# MCU.net
KiCad netlist of a schematic drawn in Altium Designer
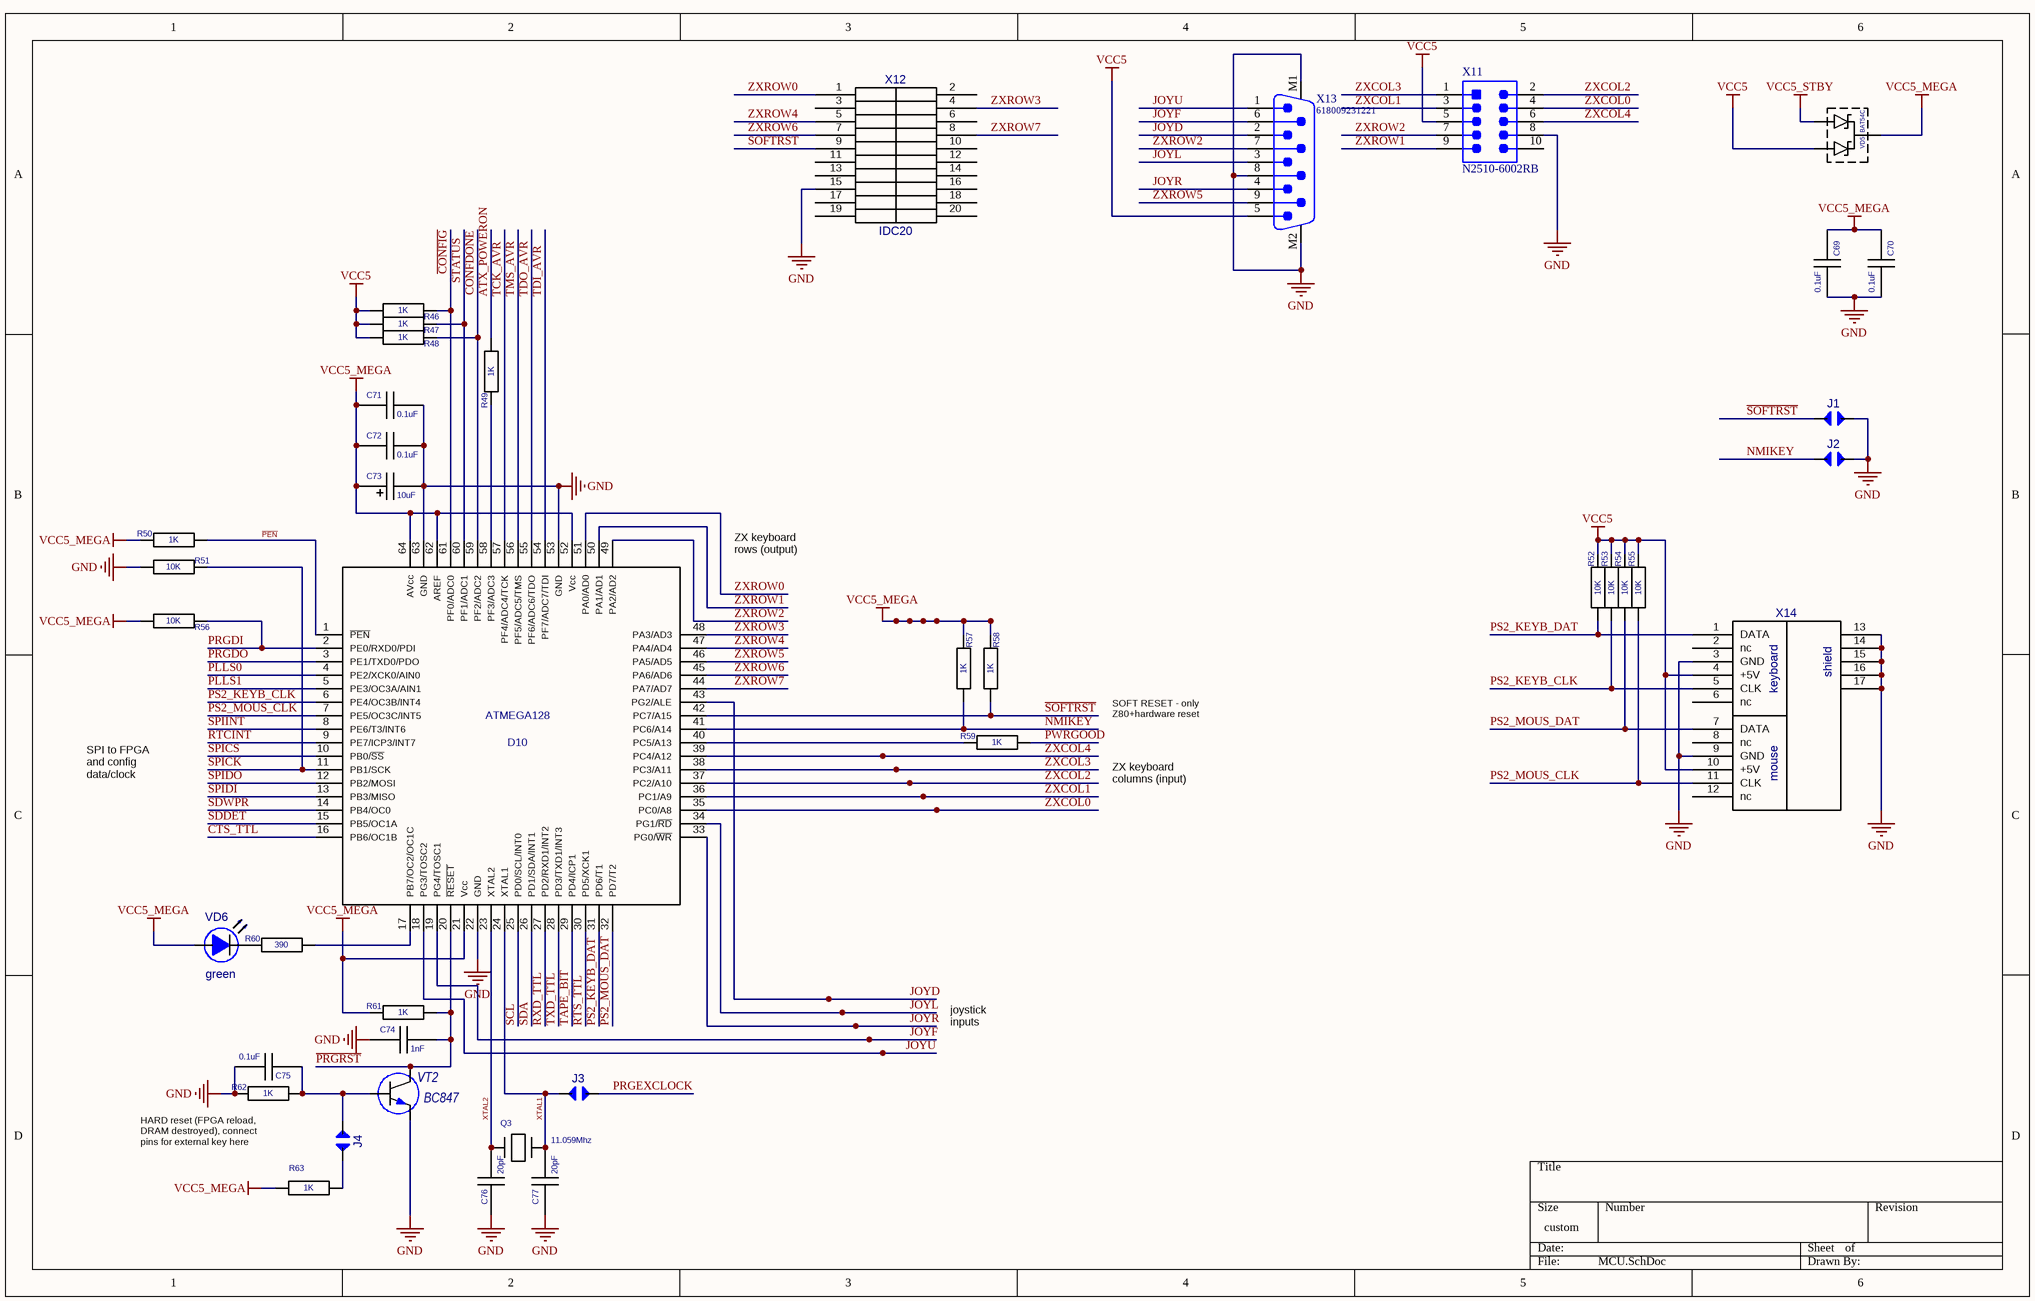
[diagram p0: MCU.SchDoc]

(export (version "E")
  (design (tool "Eeschema 10.0.6"))
  (components
    (comp (ref "C69")
      (value "0.1uF")
      (footprint "C-CHIP")
      (description "CAPCHIP")
      (libsource (lib "*") (part "CAPCHIP"))
    )
    (comp (ref "C70")
      (value "0.1uF")
      (footprint "C-CHIP")
      (description "CAPCHIP")
      (libsource (lib "*") (part "CAPCHIP"))
    )
    (comp (ref "C71")
      (value "0.1uF")
      (footprint "C-CHIP")
      (description "CAPCHIP")
      (libsource (lib "*") (part "CAPCHIP"))
    )
    (comp (ref "C72")
      (value "0.1uF")
      (footprint "C-CHIP")
      (description "CAPCHIP")
      (libsource (lib "*") (part "CAPCHIP"))
    )
    (comp (ref "C73")
      (value "10uF")
      (footprint "EC-CHIP")
      (description "ECAPCHIP")
      (libsource (lib "*") (part "ECAPCHIP"))
    )
    (comp (ref "C74")
      (value "1nF")
      (footprint "C-CHIP")
      (description "CAPCHIP")
      (libsource (lib "*") (part "CAPCHIP"))
    )
    (comp (ref "C75")
      (value "0.1uF")
      (footprint "C-CHIP")
      (description "CAPCHIP")
      (libsource (lib "*") (part "CAPCHIP"))
    )
    (comp (ref "C76")
      (value "20pF")
      (footprint "C-CHIP")
      (description "CAPCHIP")
      (libsource (lib "*") (part "CAPCHIP"))
    )
    (comp (ref "C77")
      (value "20pF")
      (footprint "C-CHIP")
      (description "CAPCHIP")
      (libsource (lib "*") (part "CAPCHIP"))
    )
    (comp (ref "D10") (value "ATMEGA128") (footprint "TQFP64X8") (libsource (lib "*") (part "ATMEGA128")))
    (comp (ref "J1")
      (value "JUMPER")
      (footprint "JUMPER")
      (description "Soft Reset Key")
      (libsource (lib "*") (part "JUMPER"))
    )
    (comp (ref "J2")
      (value "JUMPER")
      (footprint "JUMPER")
      (description "NMI Key")
      (libsource (lib "*") (part "JUMPER"))
    )
    (comp (ref "J3")
      (value "JUMPER")
      (footprint "JUMPER")
      (description "externalclock")
      (libsource (lib "*") (part "JUMPER"))
    )
    (comp (ref "J4")
      (value "JUMPER")
      (footprint "JUMPER")
      (description "Hard Reset Key")
      (libsource (lib "*") (part "JUMPER"))
    )
    (comp (ref "Q3")
      (value "11.059Mhz")
      (footprint "CRYSTAL")
      (description "Crystal")
      (fields (field (name "Comment") "QUARTZ"))
      (libsource (lib "*") (part "QUARTZ"))
    )
    (comp (ref "R46")
      (value "1K")
      (footprint "R-CHIP")
      (description "RESCHIP")
      (libsource (lib "*") (part "RESCHIP"))
    )
    (comp (ref "R47")
      (value "1K")
      (footprint "R-CHIP")
      (description "RESCHIP")
      (libsource (lib "*") (part "RESCHIP"))
    )
    (comp (ref "R48")
      (value "1K")
      (footprint "R-CHIP")
      (description "RESCHIP")
      (libsource (lib "*") (part "RESCHIP"))
    )
    (comp (ref "R49")
      (value "1K")
      (footprint "R-CHIP")
      (description "RESCHIP")
      (libsource (lib "*") (part "RESCHIP"))
    )
    (comp (ref "R50")
      (value "1K")
      (footprint "R-CHIP")
      (description "RESCHIP")
      (libsource (lib "*") (part "RESCHIP"))
    )
    (comp (ref "R51")
      (value "10K")
      (footprint "R-CHIP")
      (description "RESCHIP")
      (libsource (lib "*") (part "RESCHIP"))
    )
    (comp (ref "R52")
      (value "10K")
      (footprint "R-CHIP")
      (description "RESCHIP")
      (libsource (lib "*") (part "RESCHIP"))
    )
    (comp (ref "R53")
      (value "10K")
      (footprint "R-CHIP")
      (description "RESCHIP")
      (libsource (lib "*") (part "RESCHIP"))
    )
    (comp (ref "R54")
      (value "10K")
      (footprint "R-CHIP")
      (description "RESCHIP")
      (libsource (lib "*") (part "RESCHIP"))
    )
    (comp (ref "R55")
      (value "10K")
      (footprint "R-CHIP")
      (description "RESCHIP")
      (libsource (lib "*") (part "RESCHIP"))
    )
    (comp (ref "R56")
      (value "10K")
      (footprint "R-CHIP")
      (description "RESCHIP")
      (libsource (lib "*") (part "RESCHIP"))
    )
    (comp (ref "R57")
      (value "1K")
      (footprint "R-CHIP")
      (description "RESCHIP")
      (libsource (lib "*") (part "RESCHIP"))
    )
    (comp (ref "R58")
      (value "1K")
      (footprint "R-CHIP")
      (description "RESCHIP")
      (libsource (lib "*") (part "RESCHIP"))
    )
    (comp (ref "R59")
      (value "1K")
      (footprint "R-CHIP")
      (description "RESCHIP")
      (libsource (lib "*") (part "RESCHIP"))
    )
    (comp (ref "R60")
      (value "390")
      (footprint "R-CHIP")
      (description "RESCHIP")
      (libsource (lib "*") (part "RESCHIP"))
    )
    (comp (ref "R61")
      (value "1K")
      (footprint "R-CHIP")
      (description "RESCHIP")
      (libsource (lib "*") (part "RESCHIP"))
    )
    (comp (ref "R62")
      (value "1K")
      (footprint "R-CHIP")
      (description "RESCHIP")
      (libsource (lib "*") (part "RESCHIP"))
    )
    (comp (ref "R63")
      (value "1K")
      (footprint "R-CHIP")
      (description "RESCHIP")
      (libsource (lib "*") (part "RESCHIP"))
    )
    (comp (ref "VD5") (value "BAT54C") (footprint "SOT-23") (libsource (lib "*") (part "BAT54C")))
    (comp (ref "VD6")
      (value "green")
      (footprint "LED100")
      (description "Light Emitting Diode")
      (fields (field (name "Comment") "LED"))
      (libsource (lib "*") (part "LED"))
    )
    (comp (ref "VT2") (value "BC847") (footprint "SOT-23") (libsource (lib "*") (part "BC847")))
    (comp (ref "X11")
      (value "N2510-6002RB")
      (footprint "3M-N2510-6002-10_V")
      (fields (field (name "PARTNUMBER") "N2510") (field (name "MANUFACTURER") "3M"))
      (libsource (lib "Altium Content Vault") (part "CN-2P-M-R10"))
    )
    (comp (ref "X12") (value "IDC20") (footprint "IDC20") (libsource (lib "*") (part "IDC20")))
    (comp (ref "X13")
      (value "618009231221")
      (footprint "618009231221")
      (description "Male PCB Connector with Hex Screw WR-DSUB, 8.08 mm, Angled, 9 pins")
      (fields (field (name "MANUFACTURER") "Wurth Elektronik") (field (name "PUBLISHER") "WurthElektronik"))
      (libsource (lib "Altium Content Vault") (part "WE-CN-2S-2M-D9"))
    )
    (comp (ref "X14") (value "KEYB-MOUSE") (footprint "MDD-6FR") (libsource (lib "*") (part "KEYB-MOUSE")))
  )
  (nets
    (net (code "1") (name "/ATX_POWERON") (class "Default")
      (node (ref "R49") (pin "1") (pinfunction "i/o_1") (pintype "passive"))
    )
    (net (code "2") (name "/CONFDONE") (class "Default")
      (node (ref "D10") (pin "59") (pinfunction "PF2/ADC2_59") (pintype "passive"))
      (node (ref "R48") (pin "2") (pinfunction "i/o1_2") (pintype "passive"))
    )
    (net (code "3") (name "/CTS_TTL") (class "Default")
      (node (ref "D10") (pin "16") (pinfunction "PB6/OC1B_16") (pintype "passive"))
    )
    (net (code "4") (name "/JOYD") (class "Default")
      (node (ref "D10") (pin "43") (pinfunction "PG2/ALE_43") (pintype "passive"))
      (node (ref "X13") (pin "2") (pinfunction "2_2") (pintype "passive"))
    )
    (net (code "5") (name "/JOYF") (class "Default")
      (node (ref "D10") (pin "19") (pinfunction "PG4/TOSC1_19") (pintype "passive"))
      (node (ref "X13") (pin "6") (pinfunction "6_6") (pintype "passive"))
    )
    (net (code "6") (name "/JOYL") (class "Default")
      (node (ref "D10") (pin "34") (pinfunction "PG1/~{RD}_34") (pintype "passive"))
      (node (ref "X13") (pin "3") (pinfunction "3_3") (pintype "passive"))
    )
    (net (code "7") (name "/JOYR") (class "Default")
      (node (ref "D10") (pin "33") (pinfunction "PG0/~{WR}_33") (pintype "passive"))
      (node (ref "X13") (pin "4") (pinfunction "4_4") (pintype "passive"))
    )
    (net (code "8") (name "/JOYU") (class "Default")
      (node (ref "D10") (pin "18") (pinfunction "PG3/TOSC2_18") (pintype "passive"))
      (node (ref "X13") (pin "1") (pinfunction "1_1") (pintype "passive"))
    )
    (net (code "9") (name "/NMIKEY") (class "Default")
      (node (ref "D10") (pin "41") (pinfunction "PC6/A14_41") (pintype "passive"))
      (node (ref "J2") (pin "0") (pinfunction "1_0") (pintype "passive"))
      (node (ref "R57") (pin "1") (pinfunction "i/o_1") (pintype "passive"))
    )
    (net (code "10") (name "/PLLS0") (class "Default")
      (node (ref "D10") (pin "4") (pinfunction "PE2/XCK0/AIN0_4") (pintype "passive"))
    )
    (net (code "11") (name "/PLLS1") (class "Default")
      (node (ref "D10") (pin "5") (pinfunction "PE3/OC3A/AIN1_5") (pintype "passive"))
    )
    (net (code "12") (name "/PRGDI") (class "Default")
      (node (ref "D10") (pin "2") (pinfunction "PE0/RXD0/PDI_2") (pintype "passive"))
      (node (ref "R56") (pin "2") (pinfunction "i/o1_2") (pintype "passive"))
    )
    (net (code "13") (name "/PRGDO") (class "Default")
      (node (ref "D10") (pin "3") (pinfunction "PE1/TXD0/PDO_3") (pintype "passive"))
    )
    (net (code "14") (name "/PRGEXCLOCK") (class "Default")
      (node (ref "J3") (pin "1") (pinfunction "2_1") (pintype "passive"))
    )
    (net (code "15") (name "/PS2_KEYB_CLK") (class "Default")
      (node (ref "D10") (pin "6") (pinfunction "PE4/OC3B/INT4_6") (pintype "passive"))
      (node (ref "R53") (pin "1") (pinfunction "i/o_1") (pintype "passive"))
      (node (ref "X14") (pin "5") (pinfunction "CLK_5") (pintype "passive"))
    )
    (net (code "16") (name "/PS2_KEYB_DAT") (class "Default")
      (node (ref "D10") (pin "31") (pinfunction "PD6/T1_31") (pintype "passive"))
      (node (ref "R52") (pin "1") (pinfunction "i/o_1") (pintype "passive"))
      (node (ref "X14") (pin "1") (pinfunction "DATA_1") (pintype "passive"))
    )
    (net (code "17") (name "/PS2_MOUS_CLK") (class "Default")
      (node (ref "D10") (pin "7") (pinfunction "PE5/OC3C/INT5_7") (pintype "passive"))
      (node (ref "R55") (pin "1") (pinfunction "i/o_1") (pintype "passive"))
      (node (ref "X14") (pin "11") (pinfunction "CLK_11") (pintype "passive"))
    )
    (net (code "18") (name "/PS2_MOUS_DAT") (class "Default")
      (node (ref "D10") (pin "32") (pinfunction "PD7/T2_32") (pintype "passive"))
      (node (ref "R54") (pin "1") (pinfunction "i/o_1") (pintype "passive"))
      (node (ref "X14") (pin "7") (pinfunction "DATA_7") (pintype "passive"))
    )
    (net (code "19") (name "/PWRGOOD") (class "Default")
      (node (ref "R59") (pin "1") (pinfunction "i/o_1") (pintype "passive"))
    )
    (net (code "20") (name "/RTS_TTL") (class "Default")
      (node (ref "D10") (pin "30") (pinfunction "PD5/XCK1_30") (pintype "passive"))
    )
    (net (code "21") (name "/RXD_TTL") (class "Default")
      (node (ref "D10") (pin "27") (pinfunction "PD2/RXD1/INT2_27") (pintype "passive"))
    )
    (net (code "22") (name "/SCL") (class "Default")
      (node (ref "D10") (pin "25") (pinfunction "PD0/SCL/INT0_25") (pintype "passive"))
    )
    (net (code "23") (name "/SDA") (class "Default")
      (node (ref "D10") (pin "26") (pinfunction "PD1/SDA/INT1_26") (pintype "passive"))
    )
    (net (code "24") (name "/SDDET") (class "Default")
      (node (ref "D10") (pin "15") (pinfunction "PB5/OC1A_15") (pintype "passive"))
    )
    (net (code "25") (name "/SDWPR") (class "Default")
      (node (ref "D10") (pin "14") (pinfunction "PB4/OC0_14") (pintype "passive"))
    )
    (net (code "26") (name "/SPICK") (class "Default")
      (node (ref "D10") (pin "11") (pinfunction "PB1/SCK_11") (pintype "passive"))
      (node (ref "R51") (pin "2") (pinfunction "i/o1_2") (pintype "passive"))
    )
    (net (code "27") (name "/SPIDI") (class "Default")
      (node (ref "D10") (pin "13") (pinfunction "PB3/MISO_13") (pintype "passive"))
    )
    (net (code "28") (name "/SPIDO") (class "Default")
      (node (ref "D10") (pin "12") (pinfunction "PB2/MOSI_12") (pintype "passive"))
    )
    (net (code "29") (name "/TAPE_BIT") (class "Default")
      (node (ref "D10") (pin "29") (pinfunction "PD4/ICP1_29") (pintype "passive"))
    )
    (net (code "30") (name "/TCK_AVR") (class "Default")
      (node (ref "D10") (pin "57") (pinfunction "PF4/ADC4/TCK_57") (pintype "passive"))
    )
    (net (code "31") (name "/TDI_AVR") (class "Default")
      (node (ref "D10") (pin "54") (pinfunction "PF7/ADC7/TDI_54") (pintype "passive"))
    )
    (net (code "32") (name "/TDO_AVR") (class "Default")
      (node (ref "D10") (pin "55") (pinfunction "PF6/ADC6/TDO_55") (pintype "passive"))
    )
    (net (code "33") (name "/TMS_AVR") (class "Default")
      (node (ref "D10") (pin "56") (pinfunction "PF5/ADC5/TMS_56") (pintype "passive"))
    )
    (net (code "34") (name "/TXD_TTL") (class "Default")
      (node (ref "D10") (pin "28") (pinfunction "PD3/TXD1/INT3_28") (pintype "passive"))
    )
    (net (code "35") (name "/XTAL1") (class "Default")
      (node (ref "C77") (pin "2") (pinfunction "2_2") (pintype "passive"))
      (node (ref "D10") (pin "24") (pinfunction "XTAL1_24") (pintype "passive"))
      (node (ref "J3") (pin "0") (pinfunction "1_0") (pintype "passive"))
      (node (ref "Q3") (pin "B") (pinfunction "B_B") (pintype "passive"))
    )
    (net (code "36") (name "/XTAL2") (class "Default")
      (node (ref "C76") (pin "2") (pinfunction "2_2") (pintype "passive"))
      (node (ref "D10") (pin "23") (pinfunction "XTAL2_23") (pintype "passive"))
      (node (ref "Q3") (pin "A") (pinfunction "A_A") (pintype "passive"))
    )
    (net (code "37") (name "/ZXCOL0") (class "Default")
      (node (ref "D10") (pin "35") (pinfunction "PC0/A8_35") (pintype "passive"))
      (node (ref "X11") (pin "4") (pinfunction "4_4") (pintype "passive"))
    )
    (net (code "38") (name "/ZXCOL1") (class "Default")
      (node (ref "D10") (pin "36") (pinfunction "PC1/A9_36") (pintype "passive"))
      (node (ref "X11") (pin "3") (pinfunction "3_3") (pintype "passive"))
    )
    (net (code "39") (name "/ZXCOL2") (class "Default")
      (node (ref "D10") (pin "37") (pinfunction "PC2/A10_37") (pintype "passive"))
      (node (ref "X11") (pin "2") (pinfunction "2_2") (pintype "passive"))
    )
    (net (code "40") (name "/ZXCOL3") (class "Default")
      (node (ref "D10") (pin "38") (pinfunction "PC3/A11_38") (pintype "passive"))
      (node (ref "X11") (pin "1") (pinfunction "1_1") (pintype "passive"))
    )
    (net (code "41") (name "/ZXCOL4") (class "Default")
      (node (ref "D10") (pin "39") (pinfunction "PC4/A12_39") (pintype "passive"))
      (node (ref "X11") (pin "6") (pinfunction "6_6") (pintype "passive"))
    )
    (net (code "42") (name "/ZXROW0") (class "Default")
      (node (ref "D10") (pin "51") (pinfunction "PA0/AD0_51") (pintype "passive"))
      (node (ref "X12") (pin "1") (pinfunction "1_1") (pintype "passive"))
    )
    (net (code "43") (name "/ZXROW1") (class "Default")
      (node (ref "D10") (pin "50") (pinfunction "PA1/AD1_50") (pintype "passive"))
      (node (ref "X11") (pin "9") (pinfunction "9_9") (pintype "passive"))
    )
    (net (code "44") (name "/ZXROW2") (class "Default")
      (node (ref "D10") (pin "49") (pinfunction "PA2/AD2_49") (pintype "passive"))
      (node (ref "X11") (pin "7") (pinfunction "7_7") (pintype "passive"))
      (node (ref "X13") (pin "7") (pinfunction "7_7") (pintype "passive"))
    )
    (net (code "45") (name "/ZXROW3") (class "Default")
      (node (ref "D10") (pin "48") (pinfunction "PA3/AD3_48") (pintype "passive"))
      (node (ref "X12") (pin "4") (pinfunction "4_4") (pintype "passive"))
    )
    (net (code "46") (name "/ZXROW4") (class "Default")
      (node (ref "D10") (pin "47") (pinfunction "PA4/AD4_47") (pintype "passive"))
      (node (ref "X12") (pin "5") (pinfunction "5_5") (pintype "passive"))
    )
    (net (code "47") (name "/ZXROW5") (class "Default")
      (node (ref "D10") (pin "46") (pinfunction "PA5/AD5_46") (pintype "passive"))
      (node (ref "X13") (pin "9") (pinfunction "9_9") (pintype "passive"))
    )
    (net (code "48") (name "/ZXROW6") (class "Default")
      (node (ref "D10") (pin "45") (pinfunction "PA6/AD6_45") (pintype "passive"))
      (node (ref "X12") (pin "7") (pinfunction "7_7") (pintype "passive"))
    )
    (net (code "49") (name "/ZXROW7") (class "Default")
      (node (ref "D10") (pin "44") (pinfunction "PA7/AD7_44") (pintype "passive"))
      (node (ref "X12") (pin "8") (pinfunction "8_8") (pintype "passive"))
    )
    (net (code "50") (name "/~{CONFIG}") (class "Default")
      (node (ref "D10") (pin "61") (pinfunction "PF0/ADC0_61") (pintype "passive"))
      (node (ref "R46") (pin "2") (pinfunction "i/o1_2") (pintype "passive"))
    )
    (net (code "51") (name "/~{PEN}") (class "Default")
      (node (ref "D10") (pin "1") (pinfunction "~{PEN}_1") (pintype "passive"))
      (node (ref "R50") (pin "1") (pinfunction "i/o_1") (pintype "passive"))
    )
    (net (code "52") (name "/~{PRGRST}") (class "Default")
      (node (ref "C74") (pin "2") (pinfunction "2_2") (pintype "passive"))
      (node (ref "D10") (pin "20") (pinfunction "~{RESET}_20") (pintype "passive"))
      (node (ref "R61") (pin "1") (pinfunction "i/o_1") (pintype "passive"))
      (node (ref "VT2") (pin "3") (pinfunction "collector_3") (pintype "passive"))
    )
    (net (code "53") (name "/~{RTCINT}") (class "Default")
      (node (ref "D10") (pin "9") (pinfunction "PE7/ICP3/INT7_9") (pintype "passive"))
    )
    (net (code "54") (name "/~{SOFTRST}") (class "Default")
      (node (ref "D10") (pin "42") (pinfunction "PC7/A15_42") (pintype "passive"))
      (node (ref "J1") (pin "0") (pinfunction "1_0") (pintype "passive"))
      (node (ref "R58") (pin "1") (pinfunction "i/o_1") (pintype "passive"))
      (node (ref "X12") (pin "9") (pinfunction "9_9") (pintype "passive"))
    )
    (net (code "55") (name "/~{SPICS}") (class "Default")
      (node (ref "D10") (pin "10") (pinfunction "PB0/~{SS}_10") (pintype "passive"))
    )
    (net (code "56") (name "/~{SPIINT}") (class "Default")
      (node (ref "D10") (pin "8") (pinfunction "PE6/T3/INT6_8") (pintype "passive"))
    )
    (net (code "57") (name "/~{STATUS}") (class "Default")
      (node (ref "D10") (pin "60") (pinfunction "PF1/ADC1_60") (pintype "passive"))
      (node (ref "R47") (pin "2") (pinfunction "i/o1_2") (pintype "passive"))
    )
    (net (code "58") (name "GND") (class "Default")
      (node (ref "C69") (pin "2") (pinfunction "2_2") (pintype "passive"))
      (node (ref "C70") (pin "2") (pinfunction "2_2") (pintype "passive"))
      (node (ref "C71") (pin "2") (pinfunction "2_2") (pintype "passive"))
      (node (ref "C72") (pin "2") (pinfunction "2_2") (pintype "passive"))
      (node (ref "C73") (pin "2") (pintype "passive"))
      (node (ref "C74") (pin "1") (pinfunction "1_1") (pintype "passive"))
      (node (ref "C75") (pin "2") (pinfunction "2_2") (pintype "passive"))
      (node (ref "C76") (pin "1") (pinfunction "1_1") (pintype "passive"))
      (node (ref "C77") (pin "1") (pinfunction "1_1") (pintype "passive"))
      (node (ref "D10") (pin "22") (pinfunction "GND_22") (pintype "passive"))
      (node (ref "D10") (pin "53") (pinfunction "GND_53") (pintype "passive"))
      (node (ref "D10") (pin "63") (pinfunction "GND_63") (pintype "passive"))
      (node (ref "J1") (pin "1") (pinfunction "2_1") (pintype "passive"))
      (node (ref "J2") (pin "1") (pinfunction "2_1") (pintype "passive"))
      (node (ref "R51") (pin "1") (pinfunction "i/o_1") (pintype "passive"))
      (node (ref "R62") (pin "2") (pinfunction "i/o1_2") (pintype "passive"))
      (node (ref "VT2") (pin "2") (pinfunction "emitter_2") (pintype "passive"))
      (node (ref "X11") (pin "8") (pinfunction "8_8") (pintype "passive"))
      (node (ref "X12") (pin "15") (pinfunction "15_15") (pintype "passive"))
      (node (ref "X13") (pin "8") (pinfunction "8_8") (pintype "passive"))
      (node (ref "X13") (pin "M1") (pinfunction "M1_M1") (pintype "passive"))
      (node (ref "X13") (pin "M2") (pinfunction "M2_M2") (pintype "passive"))
      (node (ref "X14") (pin "13") (pinfunction "shield_13") (pintype "passive"))
      (node (ref "X14") (pin "14") (pinfunction "shield_14") (pintype "passive"))
      (node (ref "X14") (pin "15") (pinfunction "shield_15") (pintype "passive"))
      (node (ref "X14") (pin "16") (pinfunction "shield_16") (pintype "passive"))
      (node (ref "X14") (pin "17") (pinfunction "shield_17") (pintype "passive"))
      (node (ref "X14") (pin "3") (pinfunction "GND_3") (pintype "passive"))
      (node (ref "X14") (pin "9") (pinfunction "GND_9") (pintype "passive"))
    )
    (net (code "59") (name "Net-(D10-PB7{slash}OC2{slash}OC1C)") (class "Default")
      (node (ref "D10") (pin "17") (pinfunction "PB7/OC2/OC1C_17") (pintype "passive"))
      (node (ref "R60") (pin "1") (pinfunction "i/o_1") (pintype "passive"))
    )
    (net (code "60") (name "Net-(D10-PC5{slash}A13)") (class "Default")
      (node (ref "D10") (pin "40") (pinfunction "PC5/A13_40") (pintype "passive"))
      (node (ref "R59") (pin "2") (pinfunction "i/o1_2") (pintype "passive"))
    )
    (net (code "61") (name "Net-(D10-PF3{slash}ADC3)") (class "Default")
      (node (ref "D10") (pin "58") (pinfunction "PF3/ADC3_58") (pintype "passive"))
      (node (ref "R49") (pin "2") (pinfunction "i/o1_2") (pintype "passive"))
    )
    (net (code "62") (name "Net-(J4-1)") (class "Default")
      (node (ref "C75") (pin "1") (pinfunction "1_1") (pintype "passive"))
      (node (ref "J4") (pin "0") (pinfunction "1_0") (pintype "passive"))
      (node (ref "R62") (pin "1") (pinfunction "i/o_1") (pintype "passive"))
      (node (ref "VT2") (pin "1") (pinfunction "base_1") (pintype "passive"))
    )
    (net (code "63") (name "Net-(J4-2)") (class "Default")
      (node (ref "J4") (pin "1") (pinfunction "2_1") (pintype "passive"))
      (node (ref "R63") (pin "1") (pinfunction "i/o_1") (pintype "passive"))
    )
    (net (code "64") (name "Net-(R60-i{slash}o1)") (class "Default")
      (node (ref "R60") (pin "2") (pinfunction "i/o1_2") (pintype "passive"))
      (node (ref "VD6") (pin "K") (pinfunction "K_K") (pintype "passive"))
    )
    (net (code "65") (name "VCC5") (class "Default")
      (node (ref "R46") (pin "1") (pinfunction "i/o_1") (pintype "passive"))
      (node (ref "R47") (pin "1") (pinfunction "i/o_1") (pintype "passive"))
      (node (ref "R48") (pin "1") (pinfunction "i/o_1") (pintype "passive"))
      (node (ref "R52") (pin "2") (pinfunction "i/o1_2") (pintype "passive"))
      (node (ref "R53") (pin "2") (pinfunction "i/o1_2") (pintype "passive"))
      (node (ref "R54") (pin "2") (pinfunction "i/o1_2") (pintype "passive"))
      (node (ref "R55") (pin "2") (pinfunction "i/o1_2") (pintype "passive"))
      (node (ref "VD5") (pin "2") (pinfunction "2_2") (pintype "passive"))
      (node (ref "X11") (pin "5") (pinfunction "5_5") (pintype "passive"))
      (node (ref "X13") (pin "5") (pinfunction "5_5") (pintype "passive"))
      (node (ref "X14") (pin "10") (pinfunction "+5V_10") (pintype "passive"))
      (node (ref "X14") (pin "4") (pinfunction "+5V_4") (pintype "passive"))
    )
    (net (code "66") (name "VCC5_MEGA") (class "Default")
      (node (ref "C69") (pin "1") (pinfunction "1_1") (pintype "passive"))
      (node (ref "C70") (pin "1") (pinfunction "1_1") (pintype "passive"))
      (node (ref "C71") (pin "1") (pinfunction "1_1") (pintype "passive"))
      (node (ref "C72") (pin "1") (pinfunction "1_1") (pintype "passive"))
      (node (ref "C73") (pin "1") (pintype "passive"))
      (node (ref "D10") (pin "21") (pinfunction "Vcc_21") (pintype "passive"))
      (node (ref "D10") (pin "52") (pinfunction "Vcc_52") (pintype "passive"))
      (node (ref "D10") (pin "62") (pinfunction "AREF_62") (pintype "passive"))
      (node (ref "D10") (pin "64") (pinfunction "AVcc_64") (pintype "passive"))
      (node (ref "R50") (pin "2") (pinfunction "i/o1_2") (pintype "passive"))
      (node (ref "R56") (pin "1") (pinfunction "i/o_1") (pintype "passive"))
      (node (ref "R57") (pin "2") (pinfunction "i/o1_2") (pintype "passive"))
      (node (ref "R58") (pin "2") (pinfunction "i/o1_2") (pintype "passive"))
      (node (ref "R61") (pin "2") (pinfunction "i/o1_2") (pintype "passive"))
      (node (ref "R63") (pin "2") (pinfunction "i/o1_2") (pintype "passive"))
      (node (ref "VD5") (pin "3") (pinfunction "3_3") (pintype "passive"))
      (node (ref "VD6") (pin "A") (pinfunction "A_A") (pintype "passive"))
    )
    (net (code "67") (name "VCC5_STBY") (class "Default")
      (node (ref "VD5") (pin "1") (pinfunction "1_1") (pintype "passive"))
    )
    (net (code "68") (name "unconnected-(X11-Pad10)") (class "Default")
      (node (ref "X11") (pin "10") (pinfunction "10_10") (pintype "passive"))
    )
    (net (code "69") (name "unconnected-(X12-Pad2)") (class "Default")
      (node (ref "X12") (pin "2") (pinfunction "2_2") (pintype "passive"))
    )
    (net (code "70") (name "unconnected-(X12-Pad3)") (class "Default")
      (node (ref "X12") (pin "3") (pinfunction "3_3") (pintype "passive"))
    )
    (net (code "71") (name "unconnected-(X12-Pad6)") (class "Default")
      (node (ref "X12") (pin "6") (pinfunction "6_6") (pintype "passive"))
    )
    (net (code "72") (name "unconnected-(X12-Pad10)") (class "Default")
      (node (ref "X12") (pin "10") (pinfunction "10_10") (pintype "passive"))
    )
    (net (code "73") (name "unconnected-(X12-Pad11)") (class "Default")
      (node (ref "X12") (pin "11") (pinfunction "11_11") (pintype "passive"))
    )
    (net (code "74") (name "unconnected-(X12-Pad12)") (class "Default")
      (node (ref "X12") (pin "12") (pinfunction "12_12") (pintype "passive"))
    )
    (net (code "75") (name "unconnected-(X12-Pad13)") (class "Default")
      (node (ref "X12") (pin "13") (pinfunction "13_13") (pintype "passive"))
    )
    (net (code "76") (name "unconnected-(X12-Pad14)") (class "Default")
      (node (ref "X12") (pin "14") (pinfunction "14_14") (pintype "passive"))
    )
    (net (code "77") (name "unconnected-(X12-Pad16)") (class "Default")
      (node (ref "X12") (pin "16") (pinfunction "16_16") (pintype "passive"))
    )
    (net (code "78") (name "unconnected-(X12-Pad17)") (class "Default")
      (node (ref "X12") (pin "17") (pinfunction "17_17") (pintype "passive"))
    )
    (net (code "79") (name "unconnected-(X12-Pad18)") (class "Default")
      (node (ref "X12") (pin "18") (pinfunction "18_18") (pintype "passive"))
    )
    (net (code "80") (name "unconnected-(X12-Pad19)") (class "Default")
      (node (ref "X12") (pin "19") (pinfunction "19_19") (pintype "passive"))
    )
    (net (code "81") (name "unconnected-(X12-Pad20)") (class "Default")
      (node (ref "X12") (pin "20") (pinfunction "20_20") (pintype "passive"))
    )
    (net (code "82") (name "unconnected-(X14-nc-Pad2)") (class "Default")
      (node (ref "X14") (pin "2") (pinfunction "nc_2") (pintype "passive"))
    )
    (net (code "83") (name "unconnected-(X14-nc-Pad6)") (class "Default")
      (node (ref "X14") (pin "6") (pinfunction "nc_6") (pintype "passive"))
    )
    (net (code "84") (name "unconnected-(X14-nc-Pad8)") (class "Default")
      (node (ref "X14") (pin "8") (pinfunction "nc_8") (pintype "passive"))
    )
    (net (code "85") (name "unconnected-(X14-nc-Pad12)") (class "Default")
      (node (ref "X14") (pin "12") (pinfunction "nc_12") (pintype "passive"))
    )
  )
)
